# RFID1284.net
KiCad netlist of a schematic drawn in EAGLE
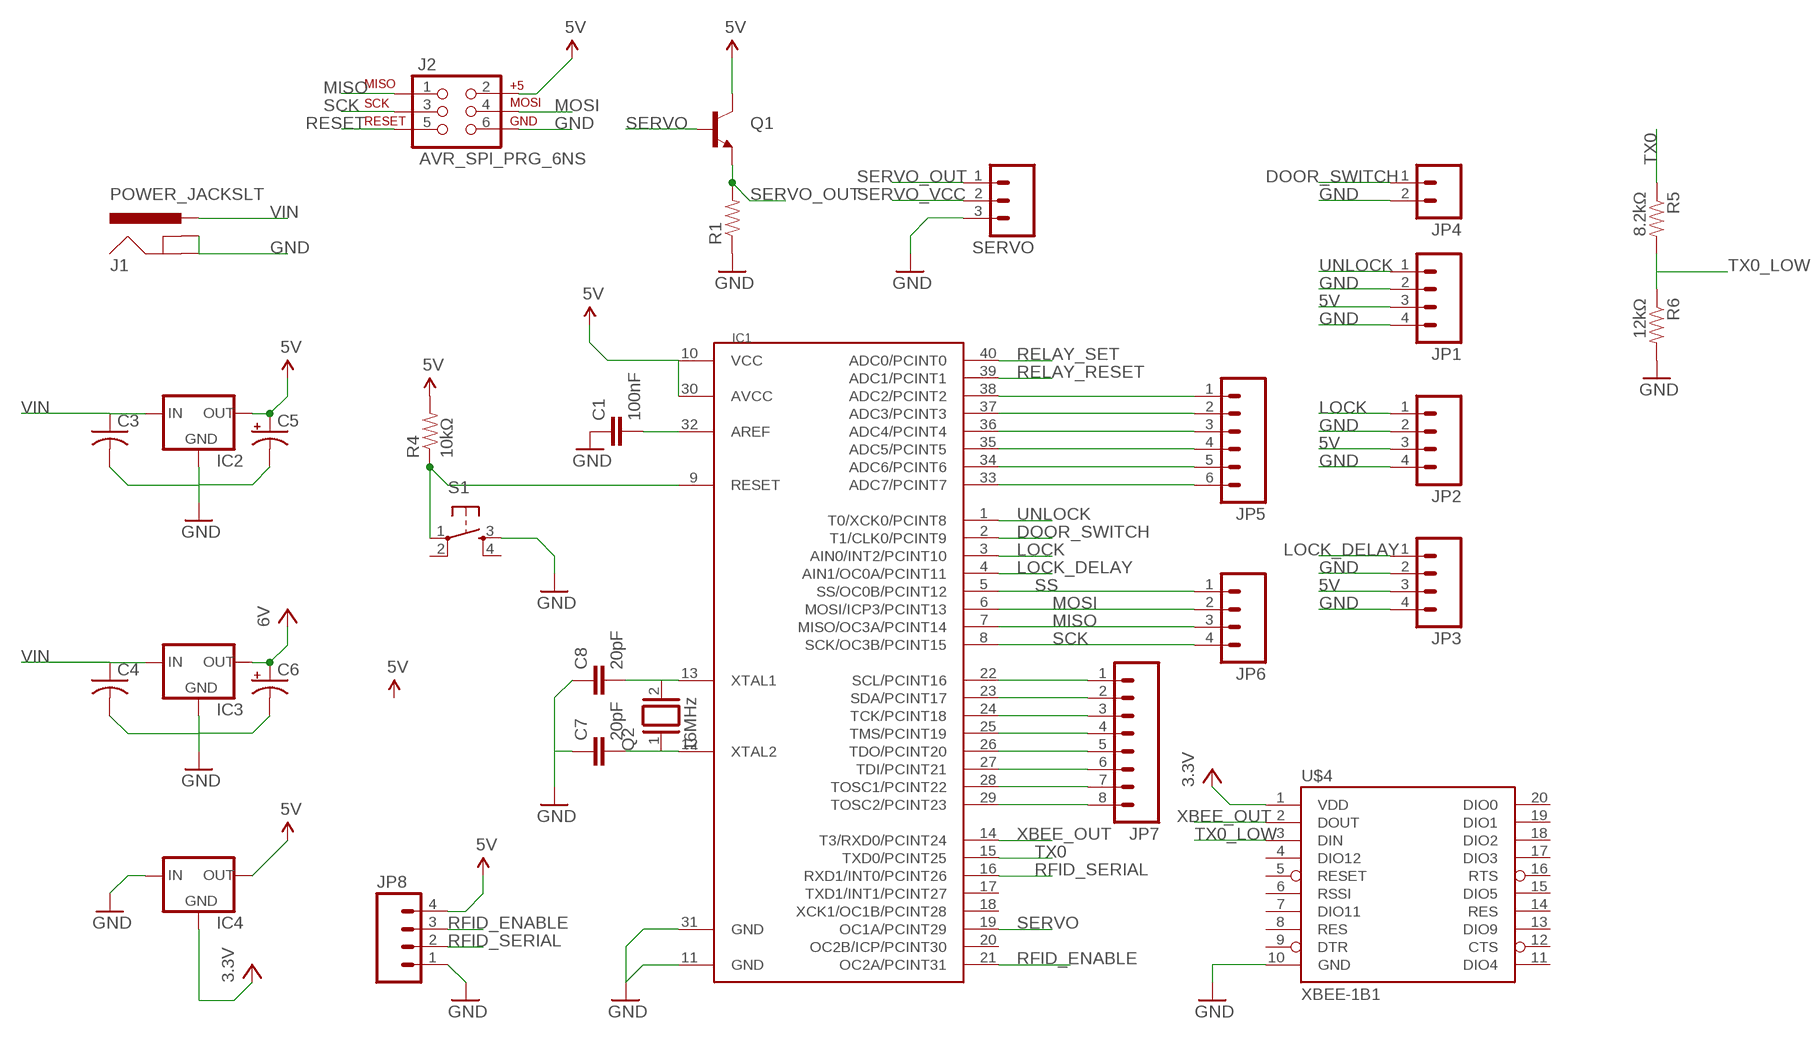
[diagram p0: schematic, sheet 1]

(export (version "E")
  (design (tool "Eeschema 10.0.6"))
  (components
    (comp (ref "C1")
      (value "100nF")
      (footprint "eagle-import:CAP-PTH-5MM")
      (libsource (lib "eagle-import") (part "CAPPTH1"))
    )
    (comp (ref "C3")
      (value "C-US025-040X050")
      (footprint "eagle-import:C025-040X050")
      (libsource (lib "eagle-import") (part "C-US025-040X050"))
    )
    (comp (ref "C4")
      (value "C-US025-040X050")
      (footprint "eagle-import:C025-040X050")
      (libsource (lib "eagle-import") (part "C-US025-040X050"))
    )
    (comp (ref "C5")
      (value "CPOL-USE2.5-7")
      (footprint "eagle-import:E2,5-7")
      (libsource (lib "eagle-import") (part "CPOL-USE2.5-7"))
    )
    (comp (ref "C6")
      (value "CPOL-USE2.5-7")
      (footprint "eagle-import:E2,5-7")
      (libsource (lib "eagle-import") (part "CPOL-USE2.5-7"))
    )
    (comp (ref "C7")
      (value "20pF")
      (footprint "eagle-import:CAP-PTH-5MM")
      (libsource (lib "eagle-import") (part "CAPPTH1"))
    )
    (comp (ref "C8")
      (value "20pF")
      (footprint "eagle-import:CAP-PTH-5MM")
      (libsource (lib "eagle-import") (part "CAPPTH1"))
    )
    (comp (ref "IC1")
      (value "MEGA1284P")
      (footprint "eagle-import:DIL40")
      (libsource (lib "eagle-import") (part "MEGA1284P"))
    )
    (comp (ref "IC2")
      (value "V_REG_78XXSINK")
      (footprint "eagle-import:TO220-IGO")
      (libsource (lib "eagle-import") (part "V_REG_78XXSINK"))
    )
    (comp (ref "IC3")
      (value "V_REG_78XXSINK")
      (footprint "eagle-import:TO220-IGO")
      (libsource (lib "eagle-import") (part "V_REG_78XXSINK"))
    )
    (comp (ref "IC4")
      (value "V_REG_78XXSINK")
      (footprint "eagle-import:TO220-IGO")
      (libsource (lib "eagle-import") (part "V_REG_78XXSINK"))
    )
    (comp (ref "J1")
      (value "POWER_JACKSLT")
      (footprint "eagle-import:POWER_JACK_SLOT")
      (libsource (lib "eagle-import") (part "POWER_JACKSLT"))
    )
    (comp (ref "J2")
      (value "AVR_SPI_PRG_6NS")
      (footprint "eagle-import:2X3-NS")
      (libsource (lib "eagle-import") (part "AVR_SPI_PRG_6NS"))
    )
    (comp (ref "JP1")
      (value "M04LOCK_LONGPADS")
      (footprint "eagle-import:1X04_LOCK_LONGPADS")
      (libsource (lib "eagle-import") (part "M04LOCK_LONGPADS"))
    )
    (comp (ref "JP2")
      (value "M04LOCK_LONGPADS")
      (footprint "eagle-import:1X04_LOCK_LONGPADS")
      (libsource (lib "eagle-import") (part "M04LOCK_LONGPADS"))
    )
    (comp (ref "JP3")
      (value "M04LOCK_LONGPADS")
      (footprint "eagle-import:1X04_LOCK_LONGPADS")
      (libsource (lib "eagle-import") (part "M04LOCK_LONGPADS"))
    )
    (comp (ref "JP4")
      (value "M02LOCK_LONGPADS")
      (footprint "eagle-import:1X02_LOCK_LONGPADS")
      (libsource (lib "eagle-import") (part "M02LOCK_LONGPADS"))
    )
    (comp (ref "JP5")
      (value "M06LOCK_LONGPADS")
      (footprint "eagle-import:1X06_LOCK_LONGPADS")
      (libsource (lib "eagle-import") (part "M06LOCK_LONGPADS"))
    )
    (comp (ref "JP6")
      (value "M04LOCK_LONGPADS")
      (footprint "eagle-import:1X04_LOCK_LONGPADS")
      (libsource (lib "eagle-import") (part "M04LOCK_LONGPADS"))
    )
    (comp (ref "JP7")
      (value "M08LOCK_LONGPADS")
      (footprint "eagle-import:1X08_LOCK_LONGPADS")
      (libsource (lib "eagle-import") (part "M08LOCK_LONGPADS"))
    )
    (comp (ref "JP8")
      (value "M04LONGPADS")
      (footprint "eagle-import:1X04_LONGPADS")
      (libsource (lib "eagle-import") (part "M04LONGPADS"))
    )
    (comp (ref "Q1")
      (value "TRANSISTOR_NPNTO-92-AMMO")
      (footprint "eagle-import:TO-92-AMMO")
      (libsource (lib "eagle-import") (part "TRANSISTOR_NPNTO-92-AMMO"))
    )
    (comp (ref "Q2")
      (value "16MHz")
      (footprint "eagle-import:QS")
      (libsource (lib "eagle-import") (part "XTAL/S"))
    )
    (comp (ref "R1")
      (value "RESISTORPTH-1/4W")
      (footprint "eagle-import:AXIAL-0.4")
      (libsource (lib "eagle-import") (part "RESISTORPTH-1/4W"))
    )
    (comp (ref "R4")
      (value "10kΩ")
      (footprint "eagle-import:AXIAL-0.4")
      (libsource (lib "eagle-import") (part "RESISTORPTH-1/4W"))
    )
    (comp (ref "R5")
      (value "8.2kΩ")
      (footprint "eagle-import:AXIAL-0.4")
      (libsource (lib "eagle-import") (part "RESISTORPTH-1/4W"))
    )
    (comp (ref "R6")
      (value "12kΩ")
      (footprint "eagle-import:AXIAL-0.4")
      (libsource (lib "eagle-import") (part "RESISTORPTH-1/4W"))
    )
    (comp (ref "S1")
      (value "TAC_SWITCHPTH")
      (footprint "eagle-import:TACTILE-PTH")
      (libsource (lib "eagle-import") (part "TAC_SWITCHPTH"))
    )
    (comp (ref "SERVO")
      (value "M03LONGPADS")
      (footprint "eagle-import:1X03_LONGPADS")
      (libsource (lib "eagle-import") (part "M03LONGPADS"))
    )
    (comp (ref "U$4")
      (value "XBEE-1B1")
      (footprint "eagle-import:XBEE-1")
      (libsource (lib "eagle-import") (part "XBEE-1B1"))
    )
  )
  (nets
    (net (code "1") (name "/DOOR_SWITCH") (class "Default")
      (node (ref "IC1") (pin "2") (pinfunction "T1/CLK0/PCINT9_2") (pintype "bidirectional"))
      (node (ref "JP4") (pin "1") (pinfunction "1_1") (pintype "passive"))
    )
    (net (code "2") (name "/LOCK") (class "Default")
      (node (ref "IC1") (pin "3") (pinfunction "AIN0/INT2/PCINT10_3") (pintype "bidirectional"))
      (node (ref "JP2") (pin "1") (pinfunction "1_1") (pintype "passive"))
    )
    (net (code "3") (name "/LOCK_DELAY") (class "Default")
      (node (ref "IC1") (pin "4") (pinfunction "AIN1/OC0A/PCINT11_4") (pintype "bidirectional"))
      (node (ref "JP3") (pin "1") (pinfunction "1_1") (pintype "passive"))
    )
    (net (code "4") (name "/MISO") (class "Default")
      (node (ref "IC1") (pin "7") (pinfunction "MISO/OC3A/PCINT14_7") (pintype "bidirectional"))
      (node (ref "J2") (pin "1") (pinfunction "1_1") (pintype "passive"))
      (node (ref "JP6") (pin "3") (pinfunction "3_3") (pintype "passive"))
    )
    (net (code "5") (name "/MOSI") (class "Default")
      (node (ref "IC1") (pin "6") (pinfunction "MOSI/ICP3/PCINT13_6") (pintype "bidirectional"))
      (node (ref "J2") (pin "4") (pinfunction "4_4") (pintype "passive"))
      (node (ref "JP6") (pin "2") (pinfunction "2_2") (pintype "passive"))
    )
    (net (code "6") (name "/RELAY_RESET") (class "Default")
      (node (ref "IC1") (pin "39") (pinfunction "ADC1/PCINT1_39") (pintype "bidirectional"))
    )
    (net (code "7") (name "/RELAY_SET") (class "Default")
      (node (ref "IC1") (pin "40") (pinfunction "ADC0/PCINT0_40") (pintype "bidirectional"))
    )
    (net (code "8") (name "/RESET") (class "Default")
      (node (ref "IC1") (pin "9") (pinfunction "RESET_9") (pintype "bidirectional"))
      (node (ref "J2") (pin "5") (pinfunction "5_5") (pintype "passive"))
      (node (ref "R4") (pin "P$1") (pinfunction "1_P$1") (pintype "passive"))
      (node (ref "S1") (pin "1") (pinfunction "1_1") (pintype "passive"))
    )
    (net (code "9") (name "/RFID_ENABLE") (class "Default")
      (node (ref "IC1") (pin "21") (pinfunction "OC2A/PCINT31_21") (pintype "bidirectional"))
      (node (ref "JP8") (pin "3") (pinfunction "3_3") (pintype "passive"))
    )
    (net (code "10") (name "/RFID_SERIAL") (class "Default")
      (node (ref "IC1") (pin "16") (pinfunction "RXD1/INT0/PCINT26_16") (pintype "bidirectional"))
      (node (ref "JP8") (pin "2") (pinfunction "2_2") (pintype "passive"))
    )
    (net (code "11") (name "/SCK") (class "Default")
      (node (ref "IC1") (pin "8") (pinfunction "SCK/OC3B/PCINT15_8") (pintype "bidirectional"))
      (node (ref "J2") (pin "3") (pinfunction "3_3") (pintype "passive"))
      (node (ref "JP6") (pin "4") (pinfunction "4_4") (pintype "passive"))
    )
    (net (code "12") (name "/SERVO") (class "Default")
      (node (ref "IC1") (pin "19") (pinfunction "OC1A/PCINT29_19") (pintype "bidirectional"))
      (node (ref "Q1") (pin "2") (pinfunction "B_2") (pintype "passive"))
    )
    (net (code "13") (name "/SERVO_OUT") (class "Default")
      (node (ref "Q1") (pin "1") (pinfunction "E_1") (pintype "passive"))
      (node (ref "R1") (pin "P$2") (pinfunction "2_P$2") (pintype "passive"))
      (node (ref "SERVO") (pin "1") (pinfunction "1_1") (pintype "passive"))
    )
    (net (code "14") (name "/SS") (class "Default")
      (node (ref "IC1") (pin "5") (pinfunction "SS/OC0B/PCINT12_5") (pintype "bidirectional"))
      (node (ref "JP6") (pin "1") (pinfunction "1_1") (pintype "passive"))
    )
    (net (code "15") (name "/TX0") (class "Default")
      (node (ref "IC1") (pin "15") (pinfunction "TXD0/PCINT25_15") (pintype "bidirectional"))
      (node (ref "R5") (pin "P$1") (pinfunction "1_P$1") (pintype "passive"))
    )
    (net (code "16") (name "/TX0_LOW") (class "Default")
      (node (ref "R5") (pin "P$2") (pinfunction "2_P$2") (pintype "passive"))
      (node (ref "R6") (pin "P$1") (pinfunction "1_P$1") (pintype "passive"))
      (node (ref "U$4") (pin "3") (pinfunction "DIN_3") (pintype "input"))
    )
    (net (code "17") (name "/UNLOCK") (class "Default")
      (node (ref "IC1") (pin "1") (pinfunction "T0/XCK0/PCINT8_1") (pintype "bidirectional"))
      (node (ref "JP1") (pin "1") (pinfunction "1_1") (pintype "passive"))
    )
    (net (code "18") (name "/VIN") (class "Default")
      (node (ref "C3") (pin "1") (pinfunction "1_1") (pintype "passive"))
      (node (ref "C4") (pin "1") (pinfunction "1_1") (pintype "passive"))
      (node (ref "IC2") (pin "IN") (pinfunction "IN_IN") (pintype "input"))
      (node (ref "IC3") (pin "IN") (pinfunction "IN_IN") (pintype "input"))
      (node (ref "J1") (pin "PWR") (pinfunction "PWR_PWR") (pintype "bidirectional"))
    )
    (net (code "19") (name "/XBEE_OUT") (class "Default")
      (node (ref "IC1") (pin "14") (pinfunction "T3/RXD0/PCINT24_14") (pintype "bidirectional"))
      (node (ref "U$4") (pin "2") (pinfunction "DOUT_2") (pintype "output"))
    )
    (net (code "20") (name "3.3V") (class "Default")
      (node (ref "IC4") (pin "GND") (pinfunction "GND_GND") (pintype "input"))
      (node (ref "U$4") (pin "1") (pinfunction "VDD_1") (pintype "power_in"))
    )
    (net (code "21") (name "5V") (class "Default")
      (node (ref "C5") (pin "+") (pinfunction "+_+") (pintype "passive"))
      (node (ref "IC1") (pin "10") (pinfunction "VCC_10") (pintype "bidirectional"))
      (node (ref "IC1") (pin "30") (pinfunction "AVCC_30") (pintype "bidirectional"))
      (node (ref "IC2") (pin "OUT") (pinfunction "OUT_OUT") (pintype "output"))
      (node (ref "IC4") (pin "OUT") (pinfunction "OUT_OUT") (pintype "output"))
      (node (ref "J2") (pin "2") (pinfunction "2_2") (pintype "passive"))
      (node (ref "JP1") (pin "3") (pinfunction "3_3") (pintype "passive"))
      (node (ref "JP2") (pin "3") (pinfunction "3_3") (pintype "passive"))
      (node (ref "JP3") (pin "3") (pinfunction "3_3") (pintype "passive"))
      (node (ref "JP8") (pin "4") (pinfunction "4_4") (pintype "passive"))
      (node (ref "Q1") (pin "3") (pinfunction "C_3") (pintype "passive"))
      (node (ref "R4") (pin "P$2") (pinfunction "2_P$2") (pintype "passive"))
    )
    (net (code "22") (name "6V") (class "Default")
      (node (ref "C6") (pin "+") (pinfunction "+_+") (pintype "passive"))
      (node (ref "IC3") (pin "OUT") (pinfunction "OUT_OUT") (pintype "output"))
      (node (ref "SERVO") (pin "2") (pinfunction "2_2") (pintype "passive"))
    )
    (net (code "23") (name "GND") (class "Default")
      (node (ref "C1") (pin "1") (pinfunction "1_1") (pintype "passive"))
      (node (ref "C3") (pin "2") (pinfunction "2_2") (pintype "passive"))
      (node (ref "C4") (pin "2") (pinfunction "2_2") (pintype "passive"))
      (node (ref "C5") (pin "-") (pinfunction "-_-") (pintype "passive"))
      (node (ref "C6") (pin "-") (pinfunction "-_-") (pintype "passive"))
      (node (ref "C7") (pin "1") (pinfunction "1_1") (pintype "passive"))
      (node (ref "C8") (pin "1") (pinfunction "1_1") (pintype "passive"))
      (node (ref "IC1") (pin "11") (pinfunction "GND_11") (pintype "bidirectional"))
      (node (ref "IC1") (pin "31") (pinfunction "GND_31") (pintype "bidirectional"))
      (node (ref "IC2") (pin "GND") (pinfunction "GND_GND") (pintype "input"))
      (node (ref "IC3") (pin "GND") (pinfunction "GND_GND") (pintype "input"))
      (node (ref "IC4") (pin "IN") (pinfunction "IN_IN") (pintype "input"))
      (node (ref "J1") (pin "GND@1") (pinfunction "GNDBREAK_GND@1") (pintype "bidirectional"))
      (node (ref "J1") (pin "GND@2") (pinfunction "GND_GND@2") (pintype "bidirectional"))
      (node (ref "J2") (pin "6") (pinfunction "6_6") (pintype "passive"))
      (node (ref "JP1") (pin "2") (pinfunction "2_2") (pintype "passive"))
      (node (ref "JP1") (pin "4") (pinfunction "4_4") (pintype "passive"))
      (node (ref "JP2") (pin "2") (pinfunction "2_2") (pintype "passive"))
      (node (ref "JP2") (pin "4") (pinfunction "4_4") (pintype "passive"))
      (node (ref "JP3") (pin "2") (pinfunction "2_2") (pintype "passive"))
      (node (ref "JP3") (pin "4") (pinfunction "4_4") (pintype "passive"))
      (node (ref "JP4") (pin "2") (pinfunction "2_2") (pintype "passive"))
      (node (ref "JP8") (pin "1") (pinfunction "1_1") (pintype "passive"))
      (node (ref "R1") (pin "P$1") (pinfunction "1_P$1") (pintype "passive"))
      (node (ref "R6") (pin "P$2") (pinfunction "2_P$2") (pintype "passive"))
      (node (ref "S1") (pin "3") (pinfunction "3_3") (pintype "passive"))
      (node (ref "SERVO") (pin "3") (pinfunction "3_3") (pintype "passive"))
      (node (ref "U$4") (pin "10") (pinfunction "GND_10") (pintype "power_in"))
    )
    (net (code "24") (name "Net-(IC1-ADC2{slash}PCINT2)") (class "Default")
      (node (ref "IC1") (pin "38") (pinfunction "ADC2/PCINT2_38") (pintype "bidirectional"))
      (node (ref "JP5") (pin "1") (pinfunction "1_1") (pintype "passive"))
    )
    (net (code "25") (name "Net-(IC1-ADC3{slash}PCINT3)") (class "Default")
      (node (ref "IC1") (pin "37") (pinfunction "ADC3/PCINT3_37") (pintype "bidirectional"))
      (node (ref "JP5") (pin "2") (pinfunction "2_2") (pintype "passive"))
    )
    (net (code "26") (name "Net-(IC1-ADC4{slash}PCINT4)") (class "Default")
      (node (ref "IC1") (pin "36") (pinfunction "ADC4/PCINT4_36") (pintype "bidirectional"))
      (node (ref "JP5") (pin "3") (pinfunction "3_3") (pintype "passive"))
    )
    (net (code "27") (name "Net-(IC1-ADC5{slash}PCINT5)") (class "Default")
      (node (ref "IC1") (pin "35") (pinfunction "ADC5/PCINT5_35") (pintype "bidirectional"))
      (node (ref "JP5") (pin "4") (pinfunction "4_4") (pintype "passive"))
    )
    (net (code "28") (name "Net-(IC1-ADC6{slash}PCINT6)") (class "Default")
      (node (ref "IC1") (pin "34") (pinfunction "ADC6/PCINT6_34") (pintype "bidirectional"))
      (node (ref "JP5") (pin "5") (pinfunction "5_5") (pintype "passive"))
    )
    (net (code "29") (name "Net-(IC1-ADC7{slash}PCINT7)") (class "Default")
      (node (ref "IC1") (pin "33") (pinfunction "ADC7/PCINT7_33") (pintype "bidirectional"))
      (node (ref "JP5") (pin "6") (pinfunction "6_6") (pintype "passive"))
    )
    (net (code "30") (name "Net-(IC1-AREF)") (class "Default")
      (node (ref "C1") (pin "2") (pinfunction "2_2") (pintype "passive"))
      (node (ref "IC1") (pin "32") (pinfunction "AREF_32") (pintype "bidirectional"))
    )
    (net (code "31") (name "Net-(IC1-SCL{slash}PCINT16)") (class "Default")
      (node (ref "IC1") (pin "22") (pinfunction "SCL/PCINT16_22") (pintype "bidirectional"))
      (node (ref "JP7") (pin "1") (pinfunction "1_1") (pintype "passive"))
    )
    (net (code "32") (name "Net-(IC1-SDA{slash}PCINT17)") (class "Default")
      (node (ref "IC1") (pin "23") (pinfunction "SDA/PCINT17_23") (pintype "bidirectional"))
      (node (ref "JP7") (pin "2") (pinfunction "2_2") (pintype "passive"))
    )
    (net (code "33") (name "Net-(IC1-TCK{slash}PCINT18)") (class "Default")
      (node (ref "IC1") (pin "24") (pinfunction "TCK/PCINT18_24") (pintype "bidirectional"))
      (node (ref "JP7") (pin "3") (pinfunction "3_3") (pintype "passive"))
    )
    (net (code "34") (name "Net-(IC1-TDI{slash}PCINT21)") (class "Default")
      (node (ref "IC1") (pin "27") (pinfunction "TDI/PCINT21_27") (pintype "bidirectional"))
      (node (ref "JP7") (pin "6") (pinfunction "6_6") (pintype "passive"))
    )
    (net (code "35") (name "Net-(IC1-TDO{slash}PCINT20)") (class "Default")
      (node (ref "IC1") (pin "26") (pinfunction "TDO/PCINT20_26") (pintype "bidirectional"))
      (node (ref "JP7") (pin "5") (pinfunction "5_5") (pintype "passive"))
    )
    (net (code "36") (name "Net-(IC1-TMS{slash}PCINT19)") (class "Default")
      (node (ref "IC1") (pin "25") (pinfunction "TMS/PCINT19_25") (pintype "bidirectional"))
      (node (ref "JP7") (pin "4") (pinfunction "4_4") (pintype "passive"))
    )
    (net (code "37") (name "Net-(IC1-TOSC1{slash}PCINT22)") (class "Default")
      (node (ref "IC1") (pin "28") (pinfunction "TOSC1/PCINT22_28") (pintype "bidirectional"))
      (node (ref "JP7") (pin "7") (pinfunction "7_7") (pintype "passive"))
    )
    (net (code "38") (name "Net-(IC1-TOSC2{slash}PCINT23)") (class "Default")
      (node (ref "IC1") (pin "29") (pinfunction "TOSC2/PCINT23_29") (pintype "bidirectional"))
      (node (ref "JP7") (pin "8") (pinfunction "8_8") (pintype "passive"))
    )
    (net (code "39") (name "Net-(IC1-XTAL1)") (class "Default")
      (node (ref "C8") (pin "2") (pinfunction "2_2") (pintype "passive"))
      (node (ref "IC1") (pin "13") (pinfunction "XTAL1_13") (pintype "bidirectional"))
      (node (ref "Q2") (pin "2") (pinfunction "2_2") (pintype "passive"))
    )
    (net (code "40") (name "Net-(IC1-XTAL2)") (class "Default")
      (node (ref "C7") (pin "2") (pinfunction "2_2") (pintype "passive"))
      (node (ref "IC1") (pin "12") (pinfunction "XTAL2_12") (pintype "bidirectional"))
      (node (ref "Q2") (pin "1") (pinfunction "1_1") (pintype "passive"))
    )
    (net (code "41") (name "unconnected-(IC1-OC2B{slash}ICP{slash}PCINT30-Pad20)") (class "Default")
      (node (ref "IC1") (pin "20") (pinfunction "OC2B/ICP/PCINT30_20") (pintype "bidirectional"))
    )
    (net (code "42") (name "unconnected-(IC1-TXD1{slash}INT1{slash}PCINT27-Pad17)") (class "Default")
      (node (ref "IC1") (pin "17") (pinfunction "TXD1/INT1/PCINT27_17") (pintype "bidirectional"))
    )
    (net (code "43") (name "unconnected-(IC1-XCK1{slash}OC1B{slash}PCINT28-Pad18)") (class "Default")
      (node (ref "IC1") (pin "18") (pinfunction "XCK1/OC1B/PCINT28_18") (pintype "bidirectional"))
    )
    (net (code "44") (name "unconnected-(S1-Pad2)") (class "Default")
      (node (ref "S1") (pin "2") (pinfunction "2_2") (pintype "passive"))
    )
    (net (code "45") (name "unconnected-(S1-Pad4)") (class "Default")
      (node (ref "S1") (pin "4") (pinfunction "4_4") (pintype "passive"))
    )
    (net (code "46") (name "unconnected-(U$4-CTS-Pad12)") (class "Default")
      (node (ref "U$4") (pin "12") (pinfunction "CTS_12") (pintype "output"))
    )
    (net (code "47") (name "unconnected-(U$4-DIO0-Pad20)") (class "Default")
      (node (ref "U$4") (pin "20") (pinfunction "DIO0_20") (pintype "bidirectional"))
    )
    (net (code "48") (name "unconnected-(U$4-DIO1-Pad19)") (class "Default")
      (node (ref "U$4") (pin "19") (pinfunction "DIO1_19") (pintype "bidirectional"))
    )
    (net (code "49") (name "unconnected-(U$4-DIO2-Pad18)") (class "Default")
      (node (ref "U$4") (pin "18") (pinfunction "DIO2_18") (pintype "bidirectional"))
    )
    (net (code "50") (name "unconnected-(U$4-DIO3-Pad17)") (class "Default")
      (node (ref "U$4") (pin "17") (pinfunction "DIO3_17") (pintype "bidirectional"))
    )
    (net (code "51") (name "unconnected-(U$4-DIO4-Pad11)") (class "Default")
      (node (ref "U$4") (pin "11") (pinfunction "DIO4_11") (pintype "bidirectional"))
    )
    (net (code "52") (name "unconnected-(U$4-DIO5-Pad15)") (class "Default")
      (node (ref "U$4") (pin "15") (pinfunction "DIO5_15") (pintype "bidirectional"))
    )
    (net (code "53") (name "unconnected-(U$4-DIO9-Pad13)") (class "Default")
      (node (ref "U$4") (pin "13") (pinfunction "DIO9_13") (pintype "bidirectional"))
    )
    (net (code "54") (name "unconnected-(U$4-DIO11-Pad7)") (class "Default")
      (node (ref "U$4") (pin "7") (pinfunction "DIO11_7") (pintype "bidirectional"))
    )
    (net (code "55") (name "unconnected-(U$4-DIO12-Pad4)") (class "Default")
      (node (ref "U$4") (pin "4") (pinfunction "DIO12_4") (pintype "bidirectional"))
    )
    (net (code "56") (name "unconnected-(U$4-DTR-Pad9)") (class "Default")
      (node (ref "U$4") (pin "9") (pinfunction "DTR_9") (pintype "bidirectional"))
    )
    (net (code "57") (name "unconnected-(U$4-RES-Pad8)") (class "Default")
      (node (ref "U$4") (pin "8") (pinfunction "RES_8") (pintype "bidirectional"))
    )
    (net (code "58") (name "unconnected-(U$4-RES-Pad14)") (class "Default")
      (node (ref "U$4") (pin "14") (pinfunction "RES_14") (pintype "bidirectional"))
    )
    (net (code "59") (name "unconnected-(U$4-RESET-Pad5)") (class "Default")
      (node (ref "U$4") (pin "5") (pinfunction "RESET_5") (pintype "input"))
    )
    (net (code "60") (name "unconnected-(U$4-RSSI-Pad6)") (class "Default")
      (node (ref "U$4") (pin "6") (pinfunction "RSSI_6") (pintype "bidirectional"))
    )
    (net (code "61") (name "unconnected-(U$4-RTS-Pad16)") (class "Default")
      (node (ref "U$4") (pin "16") (pinfunction "RTS_16") (pintype "input"))
    )
  )
)
